# Flow_Pump.net
KiCad netlist of a schematic drawn in Altium Designer
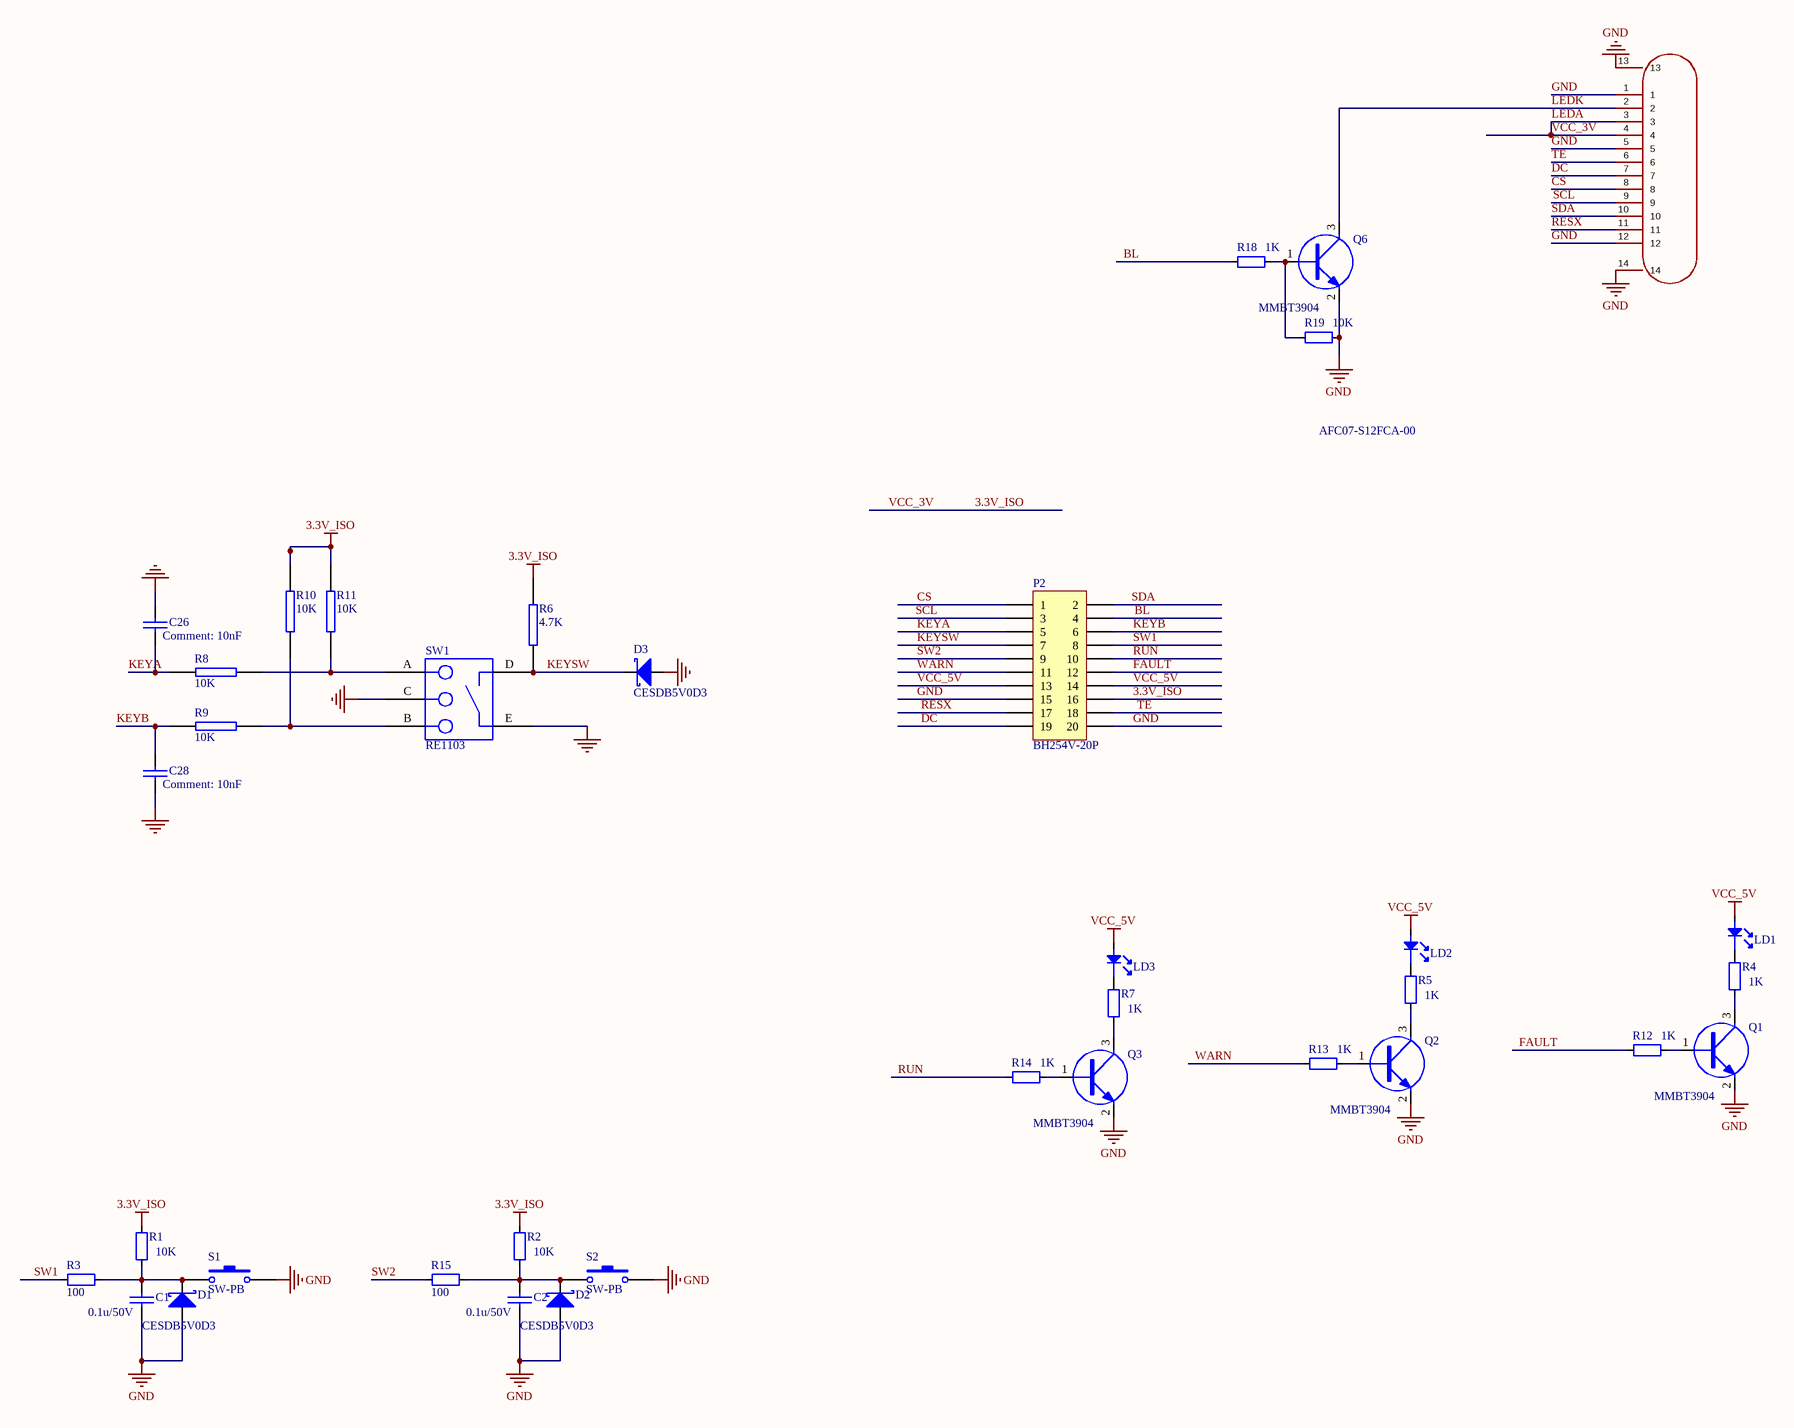
[diagram p0: Flow_Pump显示板.SchDoc]

(export (version "E")
  (design (tool "Eeschema 10.0.6"))
  (components
    (comp (ref "C1")
      (value "0.1u/50V")
      (footprint "0603C")
      (fields (field (name "Comment") "1uF/25V"))
      (libsource (lib "SM") (part "CAP"))
    )
    (comp (ref "C2")
      (value "0.1u/50V")
      (footprint "0603C")
      (fields (field (name "Comment") "1uF/25V"))
      (libsource (lib "SM") (part "CAP"))
    )
    (comp (ref "C26")
      (value "10nF")
      (footprint "0603C")
      (description "Capacitor")
      (libsource (lib "*") (part "CAP"))
    )
    (comp (ref "C28")
      (value "10nF")
      (footprint "0603C")
      (description "Capacitor")
      (libsource (lib "*") (part "CAP"))
    )
    (comp (ref "D1") (value "CESDB5V0D3") (footprint "SOD323") (libsource (lib "*") (part "DIODE S")))
    (comp (ref "D2") (value "CESDB5V0D3") (footprint "SOD323") (libsource (lib "*") (part "DIODE S")))
    (comp (ref "D3") (value "CESDB5V0D3") (footprint "SOD323") (libsource (lib "*") (part "DIODE S")))
    (comp (ref "FPC1")
      (value "AFC07-S12FCA-00")
      (footprint "FPC-SMD_12P-P0.50_AFC07-S12FCA-00")
      (libsource (lib "altium-import") (part "root_0_AFC07-S12FCA-00_"))
    )
    (comp (ref "LD1")
      (value "red")
      (footprint "0603led")
      (libsource (lib "RC_M_D_00") (part "LED_Green_19-217"))
    )
    (comp (ref "LD2")
      (value "yellowd")
      (footprint "0603led")
      (libsource (lib "RC_M_D_00") (part "LED_Green_19-217"))
    )
    (comp (ref "LD3")
      (value "Green")
      (footprint "0603led")
      (libsource (lib "RC_M_D_00") (part "LED_Green_19-217"))
    )
    (comp (ref "P2")
      (value "BH254V-20P")
      (footprint "DC-2.54-L-Z-20P")
      (description "Header, 10-Pin, Dual row")
      (fields (field (name "PUBLISHER") "Altium Limited"))
      (libsource (lib "Miscellaneous Connectors") (part "Header 10X2"))
    )
    (comp (ref "Q1")
      (value "MMBT3904")
      (footprint "SOT23-3")
      (libsource (lib "CenLib") (part "NPN_MMBT3904"))
    )
    (comp (ref "Q2")
      (value "MMBT3904")
      (footprint "SOT23-3")
      (libsource (lib "CenLib") (part "NPN_MMBT3904"))
    )
    (comp (ref "Q3")
      (value "MMBT3904")
      (footprint "SOT23-3")
      (libsource (lib "CenLib") (part "NPN_MMBT3904"))
    )
    (comp (ref "Q6")
      (value "MMBT3904")
      (footprint "SOT23-3")
      (libsource (lib "CenLib") (part "NPN_MMBT3904"))
    )
    (comp (ref "R1") (value "10K") (footprint "0603r") (libsource (lib "RC_M_D_00") (part "RES0603")))
    (comp (ref "R2") (value "10K") (footprint "0603r") (libsource (lib "RC_M_D_00") (part "RES0603")))
    (comp (ref "R3") (value "100") (footprint "0603r") (libsource (lib "RC_M_D_00") (part "RES0603")))
    (comp (ref "R4") (value "1K") (footprint "0603r") (libsource (lib "RC_M_D_00") (part "RES0603")))
    (comp (ref "R5") (value "1K") (footprint "0603r") (libsource (lib "RC_M_D_00") (part "RES0603")))
    (comp (ref "R6") (value "4.7K") (footprint "0603R") (libsource (lib "*") (part "RES2")))
    (comp (ref "R7") (value "1K") (footprint "0603r") (libsource (lib "RC_M_D_00") (part "RES0603")))
    (comp (ref "R8") (value "10K") (footprint "0603R") (libsource (lib "*") (part "RES2")))
    (comp (ref "R9") (value "10K") (footprint "0603R") (libsource (lib "*") (part "RES2")))
    (comp (ref "R10") (value "10K") (footprint "0603R") (libsource (lib "*") (part "RES2")))
    (comp (ref "R11") (value "10K") (footprint "0603R") (libsource (lib "*") (part "RES2")))
    (comp (ref "R12") (value "1K") (footprint "0603r") (libsource (lib "RC_M_D_00") (part "RES0603")))
    (comp (ref "R13") (value "1K") (footprint "0603r") (libsource (lib "RC_M_D_00") (part "RES0603")))
    (comp (ref "R14") (value "1K") (footprint "0603r") (libsource (lib "RC_M_D_00") (part "RES0603")))
    (comp (ref "R15") (value "100") (footprint "0603r") (libsource (lib "RC_M_D_00") (part "RES0603")))
    (comp (ref "R18") (value "1K") (footprint "0603r") (libsource (lib "RC_M_D_00") (part "RES0603")))
    (comp (ref "R19") (value "10K") (footprint "0603r") (libsource (lib "RC_M_D_00") (part "RES0603")))
    (comp (ref "S1")
      (value "SW-PB")
      (footprint "TSW SMD-6*6*8")
      (description "Switch")
      (fields (field (name "PUBLISHER") "Altium Limited"))
      (libsource (lib "Miscellaneous Devices") (part "SW-PB"))
    )
    (comp (ref "S2")
      (value "SW-PB")
      (footprint "TSW SMD-6*6*8")
      (description "Switch")
      (fields (field (name "PUBLISHER") "Altium Limited"))
      (libsource (lib "Miscellaneous Devices") (part "SW-PB"))
    )
    (comp (ref "SW1") (value "RE1103") (footprint "EX1103S-D2-10") (libsource (lib "*") (part "RE1103")))
  )
  (nets
    (net (code "1") (name "/BL") (class "Default")
      (node (ref "P2") (pin "4") (pinfunction "4_4") (pintype "passive"))
      (node (ref "R18") (pin "1") (pinfunction "1_1") (pintype "passive"))
    )
    (net (code "2") (name "/CS") (class "Default")
      (node (ref "FPC1") (pin "8") (pinfunction "8_8") (pintype "passive"))
      (node (ref "P2") (pin "1") (pinfunction "1_1") (pintype "passive"))
    )
    (net (code "3") (name "/DC") (class "Default")
      (node (ref "FPC1") (pin "7") (pinfunction "7_7") (pintype "passive"))
      (node (ref "P2") (pin "19") (pinfunction "19_19") (pintype "passive"))
    )
    (net (code "4") (name "/FAULT") (class "Default")
      (node (ref "P2") (pin "12") (pinfunction "12_12") (pintype "passive"))
      (node (ref "R12") (pin "1") (pinfunction "1_1") (pintype "passive"))
    )
    (net (code "5") (name "/KEYA") (class "Default")
      (node (ref "C26") (pin "2") (pinfunction "2_2") (pintype "passive"))
      (node (ref "P2") (pin "5") (pinfunction "5_5") (pintype "passive"))
      (node (ref "R8") (pin "1") (pinfunction "1_1") (pintype "passive"))
    )
    (net (code "6") (name "/KEYB") (class "Default")
      (node (ref "C28") (pin "1") (pinfunction "1_1") (pintype "passive"))
      (node (ref "P2") (pin "6") (pinfunction "6_6") (pintype "passive"))
      (node (ref "R9") (pin "1") (pinfunction "1_1") (pintype "passive"))
    )
    (net (code "7") (name "/KEYSW") (class "Default")
      (node (ref "D3") (pin "2") (pinfunction "K_2") (pintype "passive"))
      (node (ref "P2") (pin "7") (pinfunction "7_7") (pintype "passive"))
      (node (ref "R6") (pin "2") (pinfunction "2_2") (pintype "passive"))
      (node (ref "SW1") (pin "D") (pintype "passive"))
    )
    (net (code "8") (name "/LEDK") (class "Default")
      (node (ref "FPC1") (pin "2") (pinfunction "2_2") (pintype "passive"))
      (node (ref "Q6") (pin "3") (pinfunction "C_3") (pintype "passive"))
    )
    (net (code "9") (name "/RESX") (class "Default")
      (node (ref "FPC1") (pin "11") (pinfunction "11_11") (pintype "passive"))
      (node (ref "P2") (pin "17") (pinfunction "17_17") (pintype "passive"))
    )
    (net (code "10") (name "/RUN") (class "Default")
      (node (ref "P2") (pin "10") (pinfunction "10_10") (pintype "passive"))
      (node (ref "R14") (pin "1") (pinfunction "1_1") (pintype "passive"))
    )
    (net (code "11") (name "/SCL") (class "Default")
      (node (ref "FPC1") (pin "9") (pinfunction "9_9") (pintype "passive"))
      (node (ref "P2") (pin "3") (pinfunction "3_3") (pintype "passive"))
    )
    (net (code "12") (name "/SDA") (class "Default")
      (node (ref "FPC1") (pin "10") (pinfunction "10_10") (pintype "passive"))
      (node (ref "P2") (pin "2") (pinfunction "2_2") (pintype "passive"))
    )
    (net (code "13") (name "/SW1") (class "Default")
      (node (ref "P2") (pin "8") (pinfunction "8_8") (pintype "passive"))
      (node (ref "R3") (pin "1") (pinfunction "1_1") (pintype "passive"))
    )
    (net (code "14") (name "/SW2") (class "Default")
      (node (ref "P2") (pin "9") (pinfunction "9_9") (pintype "passive"))
      (node (ref "R15") (pin "1") (pinfunction "1_1") (pintype "passive"))
    )
    (net (code "15") (name "/TE") (class "Default")
      (node (ref "FPC1") (pin "6") (pinfunction "6_6") (pintype "passive"))
      (node (ref "P2") (pin "18") (pinfunction "18_18") (pintype "passive"))
    )
    (net (code "16") (name "/WARN") (class "Default")
      (node (ref "P2") (pin "11") (pinfunction "11_11") (pintype "passive"))
      (node (ref "R13") (pin "1") (pinfunction "1_1") (pintype "passive"))
    )
    (net (code "17") (name "3.3V_ISO") (class "Default")
      (node (ref "FPC1") (pin "3") (pinfunction "3_3") (pintype "passive"))
      (node (ref "FPC1") (pin "4") (pinfunction "4_4") (pintype "passive"))
      (node (ref "P2") (pin "16") (pinfunction "16_16") (pintype "passive"))
      (node (ref "R1") (pin "1") (pinfunction "1_1") (pintype "passive"))
      (node (ref "R10") (pin "2") (pinfunction "2_2") (pintype "passive"))
      (node (ref "R11") (pin "2") (pinfunction "2_2") (pintype "passive"))
      (node (ref "R2") (pin "1") (pinfunction "1_1") (pintype "passive"))
      (node (ref "R6") (pin "1") (pinfunction "1_1") (pintype "passive"))
    )
    (net (code "18") (name "GND") (class "Default")
      (node (ref "C1") (pin "1") (pinfunction "1_1") (pintype "passive"))
      (node (ref "C2") (pin "1") (pinfunction "1_1") (pintype "passive"))
      (node (ref "C26") (pin "1") (pinfunction "1_1") (pintype "passive"))
      (node (ref "C28") (pin "2") (pinfunction "2_2") (pintype "passive"))
      (node (ref "D1") (pin "1") (pinfunction "A_1") (pintype "passive"))
      (node (ref "D2") (pin "1") (pinfunction "A_1") (pintype "passive"))
      (node (ref "D3") (pin "1") (pinfunction "A_1") (pintype "passive"))
      (node (ref "FPC1") (pin "1") (pinfunction "1_1") (pintype "passive"))
      (node (ref "FPC1") (pin "12") (pinfunction "12_12") (pintype "passive"))
      (node (ref "FPC1") (pin "13") (pinfunction "13_13") (pintype "passive"))
      (node (ref "FPC1") (pin "14") (pinfunction "14_14") (pintype "passive"))
      (node (ref "FPC1") (pin "5") (pinfunction "5_5") (pintype "passive"))
      (node (ref "P2") (pin "15") (pinfunction "15_15") (pintype "passive"))
      (node (ref "P2") (pin "20") (pinfunction "20_20") (pintype "passive"))
      (node (ref "Q1") (pin "2") (pinfunction "E_2") (pintype "passive"))
      (node (ref "Q2") (pin "2") (pinfunction "E_2") (pintype "passive"))
      (node (ref "Q3") (pin "2") (pinfunction "E_2") (pintype "passive"))
      (node (ref "Q6") (pin "2") (pinfunction "E_2") (pintype "passive"))
      (node (ref "R19") (pin "2") (pinfunction "2_2") (pintype "passive"))
      (node (ref "S1") (pin "2") (pinfunction "2_2") (pintype "passive"))
      (node (ref "S2") (pin "2") (pinfunction "2_2") (pintype "passive"))
      (node (ref "SW1") (pin "C") (pintype "passive"))
      (node (ref "SW1") (pin "E") (pintype "passive"))
    )
    (net (code "19") (name "Net-(D1-K)") (class "Default")
      (node (ref "C1") (pin "2") (pinfunction "2_2") (pintype "passive"))
      (node (ref "D1") (pin "2") (pinfunction "K_2") (pintype "passive"))
      (node (ref "R1") (pin "2") (pinfunction "2_2") (pintype "passive"))
      (node (ref "R3") (pin "2") (pinfunction "2_2") (pintype "passive"))
      (node (ref "S1") (pin "1") (pinfunction "1_1") (pintype "passive"))
    )
    (net (code "20") (name "Net-(D2-K)") (class "Default")
      (node (ref "C2") (pin "2") (pinfunction "2_2") (pintype "passive"))
      (node (ref "D2") (pin "2") (pinfunction "K_2") (pintype "passive"))
      (node (ref "R15") (pin "2") (pinfunction "2_2") (pintype "passive"))
      (node (ref "R2") (pin "2") (pinfunction "2_2") (pintype "passive"))
      (node (ref "S2") (pin "1") (pinfunction "1_1") (pintype "passive"))
    )
    (net (code "21") (name "Net-(LD1-Pad2)") (class "Default")
      (node (ref "LD1") (pin "2") (pinfunction "2_2") (pintype "passive"))
      (node (ref "R4") (pin "1") (pinfunction "1_1") (pintype "passive"))
    )
    (net (code "22") (name "Net-(LD2-Pad2)") (class "Default")
      (node (ref "LD2") (pin "2") (pinfunction "2_2") (pintype "passive"))
      (node (ref "R5") (pin "1") (pinfunction "1_1") (pintype "passive"))
    )
    (net (code "23") (name "Net-(LD3-Pad2)") (class "Default")
      (node (ref "LD3") (pin "2") (pinfunction "2_2") (pintype "passive"))
      (node (ref "R7") (pin "1") (pinfunction "1_1") (pintype "passive"))
    )
    (net (code "24") (name "Net-(Q1-B)") (class "Default")
      (node (ref "Q1") (pin "1") (pinfunction "B_1") (pintype "passive"))
      (node (ref "R12") (pin "2") (pinfunction "2_2") (pintype "passive"))
    )
    (net (code "25") (name "Net-(Q1-C)") (class "Default")
      (node (ref "Q1") (pin "3") (pinfunction "C_3") (pintype "passive"))
      (node (ref "R4") (pin "2") (pinfunction "2_2") (pintype "passive"))
    )
    (net (code "26") (name "Net-(Q2-B)") (class "Default")
      (node (ref "Q2") (pin "1") (pinfunction "B_1") (pintype "passive"))
      (node (ref "R13") (pin "2") (pinfunction "2_2") (pintype "passive"))
    )
    (net (code "27") (name "Net-(Q2-C)") (class "Default")
      (node (ref "Q2") (pin "3") (pinfunction "C_3") (pintype "passive"))
      (node (ref "R5") (pin "2") (pinfunction "2_2") (pintype "passive"))
    )
    (net (code "28") (name "Net-(Q3-B)") (class "Default")
      (node (ref "Q3") (pin "1") (pinfunction "B_1") (pintype "passive"))
      (node (ref "R14") (pin "2") (pinfunction "2_2") (pintype "passive"))
    )
    (net (code "29") (name "Net-(Q3-C)") (class "Default")
      (node (ref "Q3") (pin "3") (pinfunction "C_3") (pintype "passive"))
      (node (ref "R7") (pin "2") (pinfunction "2_2") (pintype "passive"))
    )
    (net (code "30") (name "Net-(Q6-B)") (class "Default")
      (node (ref "Q6") (pin "1") (pinfunction "B_1") (pintype "passive"))
      (node (ref "R18") (pin "2") (pinfunction "2_2") (pintype "passive"))
      (node (ref "R19") (pin "1") (pinfunction "1_1") (pintype "passive"))
    )
    (net (code "31") (name "Net-(R10-Pad1)") (class "Default")
      (node (ref "R10") (pin "1") (pinfunction "1_1") (pintype "passive"))
      (node (ref "R9") (pin "2") (pinfunction "2_2") (pintype "passive"))
      (node (ref "SW1") (pin "B") (pintype "passive"))
    )
    (net (code "32") (name "Net-(R11-Pad1)") (class "Default")
      (node (ref "R11") (pin "1") (pinfunction "1_1") (pintype "passive"))
      (node (ref "R8") (pin "2") (pinfunction "2_2") (pintype "passive"))
      (node (ref "SW1") (pin "A") (pintype "passive"))
    )
    (net (code "33") (name "VCC_5V") (class "Default")
      (node (ref "LD1") (pin "1") (pinfunction "1_1") (pintype "passive"))
      (node (ref "LD2") (pin "1") (pinfunction "1_1") (pintype "passive"))
      (node (ref "LD3") (pin "1") (pinfunction "1_1") (pintype "passive"))
      (node (ref "P2") (pin "13") (pinfunction "13_13") (pintype "passive"))
      (node (ref "P2") (pin "14") (pinfunction "14_14") (pintype "passive"))
    )
  )
)
